# IOTLoRaSmartGreenhouseGateway.net
KiCad netlist of a schematic drawn in Altium Designer
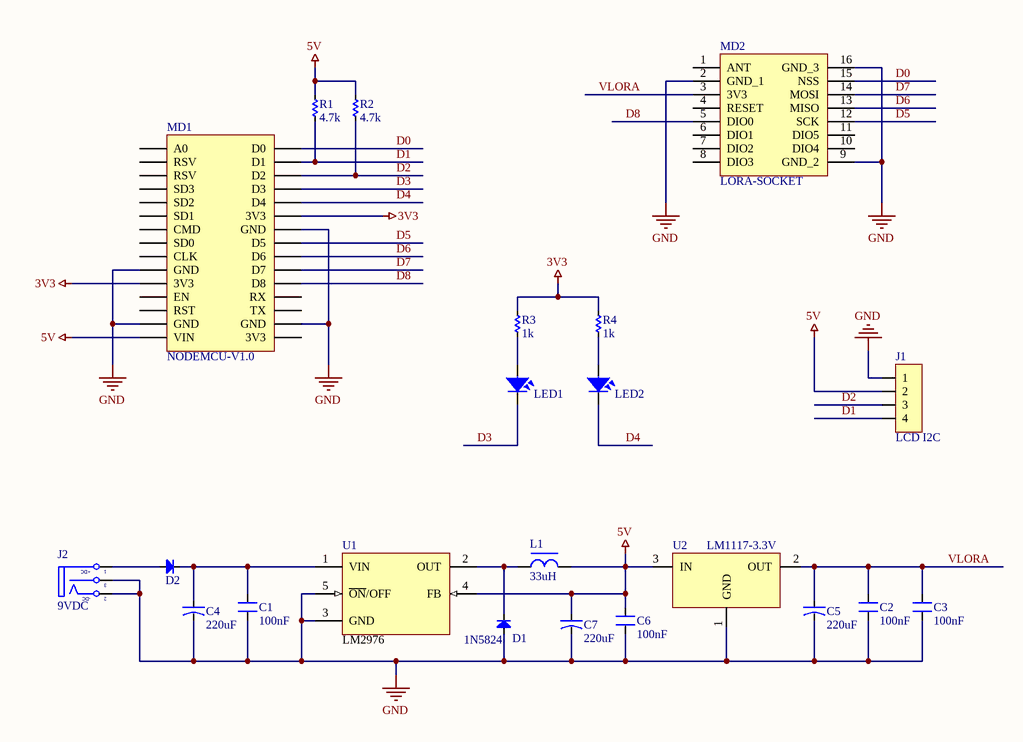
[diagram p0: IOTLoRaSmartGreenhouseGateway.SchDoc]

(export (version "E")
  (design (tool "Eeschema 10.0.6"))
  (components
    (comp (ref "C1") (value "100nF") (footprint "CN1.5") (libsource (lib "LIBRARY") (part "CN")))
    (comp (ref "C2") (value "100nF") (footprint "CN1.5") (libsource (lib "LIBRARY") (part "CN")))
    (comp (ref "C3") (value "100nF") (footprint "CN1.5") (libsource (lib "LIBRARY") (part "CN")))
    (comp (ref "C4")
      (value "220uF")
      (footprint "CA-ALU-8")
      (description "Capacitor (Semiconductor SIM Model)")
      (fields (field (name "PUBLISHER") "Altium Limited"))
      (libsource (lib "LIBRARY") (part "CN-ALU-DIP"))
    )
    (comp (ref "C5")
      (value "220uF")
      (footprint "CA-ALU-8")
      (description "Capacitor (Semiconductor SIM Model)")
      (fields (field (name "PUBLISHER") "Altium Limited"))
      (libsource (lib "LIBRARY") (part "CN-ALU-DIP"))
    )
    (comp (ref "C6") (value "100nF") (footprint "CN1.5") (libsource (lib "LIBRARY") (part "CN")))
    (comp (ref "C7")
      (value "220uF")
      (footprint "CA-ALU-8")
      (description "Capacitor (Semiconductor SIM Model)")
      (fields (field (name "PUBLISHER") "Altium Limited"))
      (libsource (lib "LIBRARY") (part "CN-ALU-DIP"))
    )
    (comp (ref "D1")
      (value "1N5824")
      (footprint "DIO-5A")
      (description "Default Diode")
      (fields (field (name "PUBLISHER") "Altium Limited"))
      (libsource (lib "LIBRARY") (part "Diode"))
    )
    (comp (ref "D2")
      (value "Diode")
      (footprint "DIO-3A")
      (description "Default Diode")
      (fields (field (name "PUBLISHER") "Altium Limited"))
      (libsource (lib "LIBRARY") (part "Diode"))
    )
    (comp (ref "J1")
      (value "LCD I2C")
      (footprint "JP4-D1C")
      (description "WR-PHD 2.54 mm Angled Socket Header")
      (fields
        (field (name "MANUFACTURER") "Würth Elektronik eiSos GmbH")
        (field (name "PARTNO") "613004143121")
        (field (name "CREATED BY") "Karrer Zheng")
      )
      (libsource (lib "LIBRARY") (part "JP4"))
    )
    (comp (ref "J2")
      (value "9VDC")
      (footprint "DC0")
      (description "Jac DC input")
      (libsource (lib "LIBRARY") (part "DCIN"))
    )
    (comp (ref "L1")
      (value "33uH")
      (footprint "L-DIP-M-10")
      (description "Inductor")
      (libsource (lib "LIBRARY") (part "L-DIP-1"))
    )
    (comp (ref "LED1")
      (value "LED")
      (footprint "LED-3MM-BLUE")
      (description "LED Single colour Green and Red")
      (libsource (lib "LIBRARY") (part "LED"))
    )
    (comp (ref "LED2")
      (value "LED")
      (footprint "LED-3MM-BLUE")
      (description "LED Single colour Green and Red")
      (libsource (lib "LIBRARY") (part "LED"))
    )
    (comp (ref "MD1")
      (value "NODEMCU-V1.0")
      (footprint "NODEMCU-V1.0")
      (description "KIT NodeMCU v1.0")
      (libsource (lib "phatvu1294_Lib") (part "NODEMCU-V1.0"))
    )
    (comp (ref "MD2")
      (value "LORA-SOCKET")
      (footprint "LORA-SOCKET")
      (description "Socket LoRa RA01 va RA02")
      (libsource (lib "User") (part "LORA-SOCKET"))
    )
    (comp (ref "R1")
      (value "4.7k")
      (footprint "RES-1/4W")
      (description "Res")
      (fields
        (field (name "MANUFACTURER") "Generic Components")
        (field (name "PUBLISHER") "Altium Hobart Technology Centre")
      )
      (libsource (lib "LIBRARY") (part "Res"))
    )
    (comp (ref "R2")
      (value "4.7k")
      (footprint "RES-1/4W")
      (description "Res")
      (fields
        (field (name "MANUFACTURER") "Generic Components")
        (field (name "PUBLISHER") "Altium Hobart Technology Centre")
      )
      (libsource (lib "LIBRARY") (part "Res"))
    )
    (comp (ref "R3")
      (value "1k")
      (footprint "RES-1/4W")
      (description "Res")
      (fields
        (field (name "MANUFACTURER") "Generic Components")
        (field (name "PUBLISHER") "Altium Hobart Technology Centre")
      )
      (libsource (lib "LIBRARY") (part "Res"))
    )
    (comp (ref "R4")
      (value "1k")
      (footprint "RES-1/4W")
      (description "Res")
      (fields
        (field (name "MANUFACTURER") "Generic Components")
        (field (name "PUBLISHER") "Altium Hobart Technology Centre")
      )
      (libsource (lib "LIBRARY") (part "Res"))
    )
    (comp (ref "U1") (value "LM2976") (footprint "TO263") (libsource (lib "LIBRARY") (part "LM2596")))
    (comp (ref "U2")
      (value "LM1117-3.3V")
      (footprint "SOT223")
      (description "800mA Low-Dropout Linear Regulator")
      (fields (field (name "CREATOR") "Nguyen Ba Bien"))
      (libsource (lib "LIBRARY") (part "LM1117"))
    )
  )
  (nets
    (net (code "1") (name "/D0") (class "Default")
      (node (ref "MD1") (pin "D0") (pinfunction "D0_D0") (pintype "passive"))
      (node (ref "MD2") (pin "15") (pinfunction "NSS_15") (pintype "passive"))
    )
    (net (code "2") (name "/D1") (class "Default")
      (node (ref "J1") (pin "4") (pinfunction "4_4") (pintype "passive"))
      (node (ref "MD1") (pin "D1") (pinfunction "D1_D1") (pintype "passive"))
      (node (ref "R1") (pin "2") (pinfunction "2_2") (pintype "passive"))
    )
    (net (code "3") (name "/D2") (class "Default")
      (node (ref "J1") (pin "3") (pinfunction "3_3") (pintype "passive"))
      (node (ref "MD1") (pin "D2") (pinfunction "D2_D2") (pintype "passive"))
      (node (ref "R2") (pin "2") (pinfunction "2_2") (pintype "passive"))
    )
    (net (code "4") (name "/D3") (class "Default")
      (node (ref "LED1") (pin "2") (pinfunction "2_2") (pintype "passive"))
      (node (ref "MD1") (pin "D3") (pinfunction "D3_D3") (pintype "passive"))
    )
    (net (code "5") (name "/D4") (class "Default")
      (node (ref "LED2") (pin "2") (pinfunction "2_2") (pintype "passive"))
      (node (ref "MD1") (pin "D4") (pinfunction "D4_D4") (pintype "passive"))
    )
    (net (code "6") (name "/D5") (class "Default")
      (node (ref "MD1") (pin "D5") (pinfunction "D5_D5") (pintype "passive"))
      (node (ref "MD2") (pin "12") (pinfunction "SCK_12") (pintype "passive"))
    )
    (net (code "7") (name "/D6") (class "Default")
      (node (ref "MD1") (pin "D6") (pinfunction "D6_D6") (pintype "passive"))
      (node (ref "MD2") (pin "13") (pinfunction "MISO_13") (pintype "passive"))
    )
    (net (code "8") (name "/D7") (class "Default")
      (node (ref "MD1") (pin "D7") (pinfunction "D7_D7") (pintype "passive"))
      (node (ref "MD2") (pin "14") (pinfunction "MOSI_14") (pintype "passive"))
    )
    (net (code "9") (name "/D8") (class "Default")
      (node (ref "MD1") (pin "D8") (pinfunction "D8_D8") (pintype "passive"))
      (node (ref "MD2") (pin "5") (pinfunction "DIO0_5") (pintype "passive"))
    )
    (net (code "10") (name "/VLORA") (class "Default")
      (node (ref "C2") (pin "1") (pinfunction "1_1") (pintype "passive"))
      (node (ref "C3") (pin "1") (pinfunction "1_1") (pintype "passive"))
      (node (ref "C5") (pin "1") (pinfunction "1_1") (pintype "passive"))
      (node (ref "MD2") (pin "3") (pinfunction "3V3_3") (pintype "passive"))
      (node (ref "U2") (pin "2") (pinfunction "OUT_2") (pintype "passive"))
    )
    (net (code "11") (name "3V3") (class "Default")
      (node (ref "MD1") (pin "3V3") (pinfunction "3V3_3V3") (pintype "power_in"))
      (node (ref "R3") (pin "1") (pinfunction "1_1") (pintype "passive"))
      (node (ref "R4") (pin "1") (pinfunction "1_1") (pintype "passive"))
    )
    (net (code "12") (name "5V") (class "Default")
      (node (ref "C6") (pin "1") (pinfunction "1_1") (pintype "passive"))
      (node (ref "C7") (pin "1") (pinfunction "1_1") (pintype "passive"))
      (node (ref "J1") (pin "2") (pinfunction "2_2") (pintype "passive"))
      (node (ref "L1") (pin "2") (pinfunction "2_2") (pintype "passive"))
      (node (ref "MD1") (pin "VIN") (pinfunction "VIN_VIN") (pintype "power_in"))
      (node (ref "R1") (pin "1") (pinfunction "1_1") (pintype "passive"))
      (node (ref "R2") (pin "1") (pinfunction "1_1") (pintype "passive"))
      (node (ref "U1") (pin "4") (pinfunction "FB_4") (pintype "input"))
      (node (ref "U2") (pin "3") (pinfunction "IN_3") (pintype "passive"))
    )
    (net (code "13") (name "GND") (class "Default")
      (node (ref "C1") (pin "2") (pinfunction "2_2") (pintype "passive"))
      (node (ref "C2") (pin "2") (pinfunction "2_2") (pintype "passive"))
      (node (ref "C3") (pin "2") (pinfunction "2_2") (pintype "passive"))
      (node (ref "C4") (pin "2") (pinfunction "2_2") (pintype "passive"))
      (node (ref "C5") (pin "2") (pinfunction "2_2") (pintype "passive"))
      (node (ref "C6") (pin "2") (pinfunction "2_2") (pintype "passive"))
      (node (ref "C7") (pin "2") (pinfunction "2_2") (pintype "passive"))
      (node (ref "D1") (pin "1") (pinfunction "A_1") (pintype "passive"))
      (node (ref "J1") (pin "1") (pinfunction "1_1") (pintype "passive"))
      (node (ref "J2") (pin "2") (pinfunction "TN_2") (pintype "passive"))
      (node (ref "J2") (pin "3") (pinfunction "S_3") (pintype "power_in"))
      (node (ref "MD1") (pin "GND") (pinfunction "GND_GND") (pintype "power_in"))
      (node (ref "MD2") (pin "16") (pinfunction "GND_3_16") (pintype "passive"))
      (node (ref "MD2") (pin "2") (pinfunction "GND_1_2") (pintype "passive"))
      (node (ref "MD2") (pin "9") (pinfunction "GND_2_9") (pintype "passive"))
      (node (ref "U1") (pin "3") (pinfunction "GND_3") (pintype "power_in"))
      (node (ref "U1") (pin "5") (pinfunction "~{ON}/OFF_5") (pintype "input"))
      (node (ref "U2") (pin "1") (pinfunction "GND_1") (pintype "passive"))
    )
    (net (code "14") (name "Net-(D1-K)") (class "Default")
      (node (ref "D1") (pin "2") (pinfunction "K_2") (pintype "passive"))
      (node (ref "L1") (pin "1") (pinfunction "1_1") (pintype "passive"))
      (node (ref "U1") (pin "2") (pinfunction "OUT_2") (pintype "power_in"))
    )
    (net (code "15") (name "Net-(D2-A)") (class "Default")
      (node (ref "D2") (pin "1") (pinfunction "A_1") (pintype "passive"))
      (node (ref "J2") (pin "1") (pinfunction "T_1") (pintype "passive"))
    )
    (net (code "16") (name "Net-(D2-K)") (class "Default")
      (node (ref "C1") (pin "1") (pinfunction "1_1") (pintype "passive"))
      (node (ref "C4") (pin "1") (pinfunction "1_1") (pintype "passive"))
      (node (ref "D2") (pin "2") (pinfunction "K_2") (pintype "passive"))
      (node (ref "U1") (pin "1") (pinfunction "VIN_1") (pintype "power_in"))
    )
    (net (code "17") (name "Net-(LED1-Pad1)") (class "Default")
      (node (ref "LED1") (pin "1") (pinfunction "1_1") (pintype "passive"))
      (node (ref "R3") (pin "2") (pinfunction "2_2") (pintype "passive"))
    )
    (net (code "18") (name "Net-(LED2-Pad1)") (class "Default")
      (node (ref "LED2") (pin "1") (pinfunction "1_1") (pintype "passive"))
      (node (ref "R4") (pin "2") (pinfunction "2_2") (pintype "passive"))
    )
    (net (code "19") (name "unconnected-(MD1-Pad3V3)") (class "Default")
      (node (ref "MD1") (pin "3V3") (pinfunction "3V3_3V3") (pintype "power_in"))
    )
    (net (code "20") (name "unconnected-(MD1-PadA0)") (class "Default")
      (node (ref "MD1") (pin "A0") (pinfunction "A0_A0") (pintype "passive"))
    )
    (net (code "21") (name "unconnected-(MD1-PadCLK)") (class "Default")
      (node (ref "MD1") (pin "CLK") (pinfunction "CLK_CLK") (pintype "passive"))
    )
    (net (code "22") (name "unconnected-(MD1-PadCMD)") (class "Default")
      (node (ref "MD1") (pin "CMD") (pinfunction "CMD_CMD") (pintype "passive"))
    )
    (net (code "23") (name "unconnected-(MD1-PadEN)") (class "Default")
      (node (ref "MD1") (pin "EN") (pinfunction "EN_EN") (pintype "passive"))
    )
    (net (code "24") (name "unconnected-(MD1-PadRST)") (class "Default")
      (node (ref "MD1") (pin "RST") (pinfunction "RST_RST") (pintype "passive"))
    )
    (net (code "25") (name "unconnected-(MD1-PadRSV)") (class "Default")
      (node (ref "MD1") (pin "RSV") (pinfunction "RSV_RSV") (pintype "passive"))
    )
    (net (code "26") (name "unconnected-(MD1-PadRSV)_1") (class "Default")
      (node (ref "MD1") (pin "RSV") (pinfunction "RSV_RSV") (pintype "passive"))
    )
    (net (code "27") (name "unconnected-(MD1-PadRX)") (class "Default")
      (node (ref "MD1") (pin "RX") (pinfunction "RX_RX") (pintype "passive"))
    )
    (net (code "28") (name "unconnected-(MD1-PadSD0)") (class "Default")
      (node (ref "MD1") (pin "SD0") (pinfunction "SD0_SD0") (pintype "passive"))
    )
    (net (code "29") (name "unconnected-(MD1-PadSD1)") (class "Default")
      (node (ref "MD1") (pin "SD1") (pinfunction "SD1_SD1") (pintype "passive"))
    )
    (net (code "30") (name "unconnected-(MD1-PadSD2)") (class "Default")
      (node (ref "MD1") (pin "SD2") (pinfunction "SD2_SD2") (pintype "passive"))
    )
    (net (code "31") (name "unconnected-(MD1-PadSD3)") (class "Default")
      (node (ref "MD1") (pin "SD3") (pinfunction "SD3_SD3") (pintype "passive"))
    )
    (net (code "32") (name "unconnected-(MD1-PadTX)") (class "Default")
      (node (ref "MD1") (pin "TX") (pinfunction "TX_TX") (pintype "passive"))
    )
    (net (code "33") (name "unconnected-(MD2-ANT-Pad1)") (class "Default")
      (node (ref "MD2") (pin "1") (pinfunction "ANT_1") (pintype "passive"))
    )
    (net (code "34") (name "unconnected-(MD2-DIO1-Pad6)") (class "Default")
      (node (ref "MD2") (pin "6") (pinfunction "DIO1_6") (pintype "passive"))
    )
    (net (code "35") (name "unconnected-(MD2-DIO2-Pad7)") (class "Default")
      (node (ref "MD2") (pin "7") (pinfunction "DIO2_7") (pintype "passive"))
    )
    (net (code "36") (name "unconnected-(MD2-DIO3-Pad8)") (class "Default")
      (node (ref "MD2") (pin "8") (pinfunction "DIO3_8") (pintype "passive"))
    )
    (net (code "37") (name "unconnected-(MD2-DIO4-Pad10)") (class "Default")
      (node (ref "MD2") (pin "10") (pinfunction "DIO4_10") (pintype "passive"))
    )
    (net (code "38") (name "unconnected-(MD2-DIO5-Pad11)") (class "Default")
      (node (ref "MD2") (pin "11") (pinfunction "DIO5_11") (pintype "passive"))
    )
    (net (code "39") (name "unconnected-(MD2-RESET-Pad4)") (class "Default")
      (node (ref "MD2") (pin "4") (pinfunction "RESET_4") (pintype "passive"))
    )
  )
)
